# RP2350A.net
KiCad netlist of a schematic drawn in Altium Designer
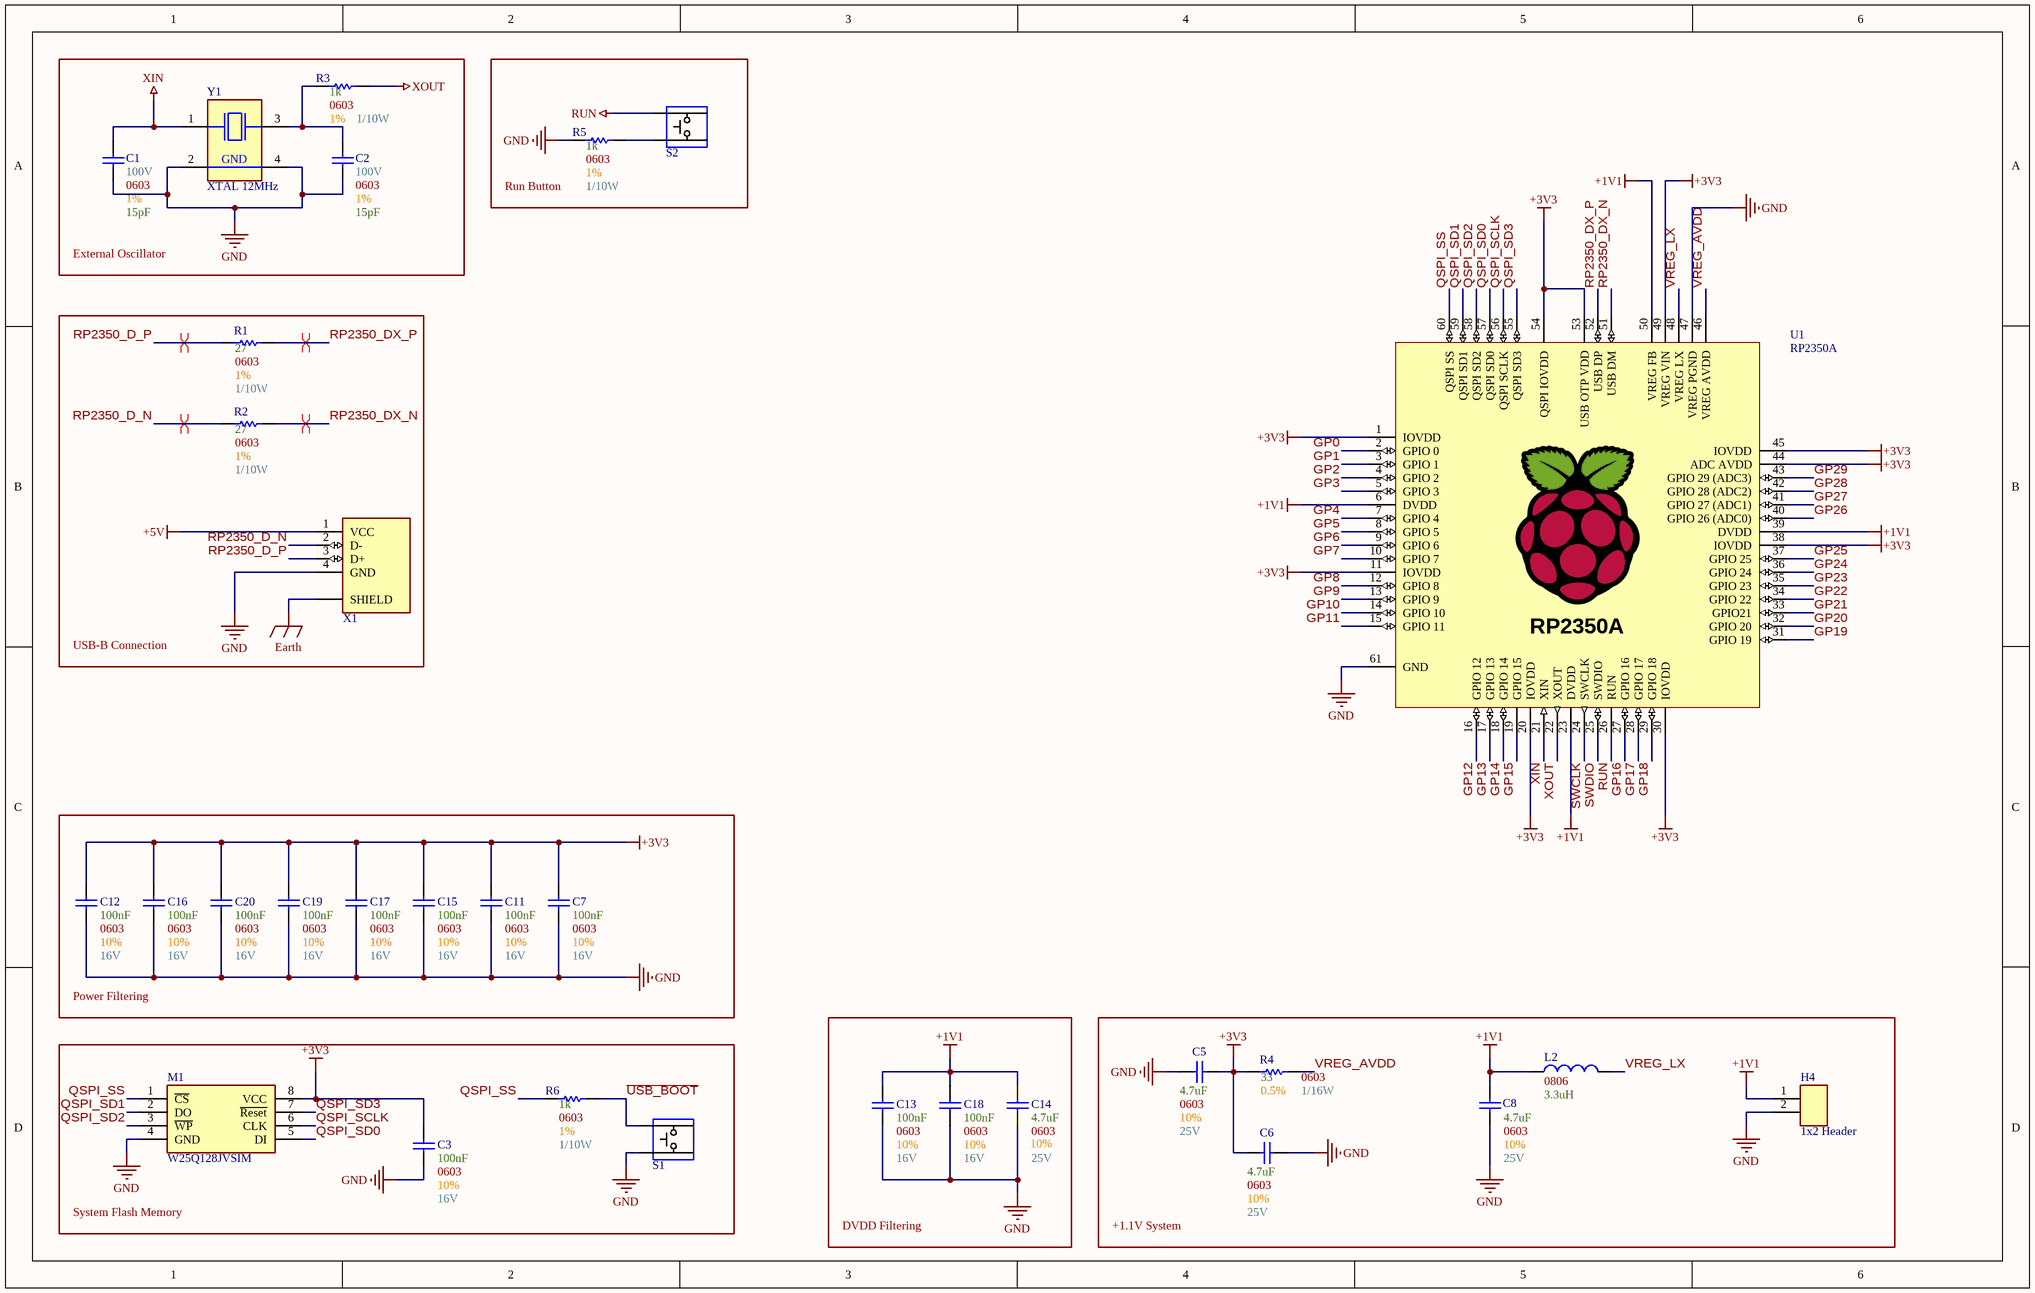
[diagram p0: RP2350A.SchDoc]

(export (version "E")
  (design (tool "Eeschema 10.0.6"))
  (components
    (comp (ref "C1")
      (value "[Cap] 0603 15pF 1% 100V")
      (footprint "[Cap] SMD 0603")
      (description "GCM1885C2A150FA16D")
      (fields
        (field (name "MAX VOLTAGE") "100V")
        (field (name "SIZE PACKAGE") "0603")
        (field (name "TOLERANCE") "1%")
        (field (name "CAPACITANCE") "15pF")
      )
      (libsource (lib "Capacitors") (part "[Cap] 0603 15pF 1% 100V"))
    )
    (comp (ref "C2")
      (value "[Cap] 0603 15pF 1% 100V")
      (footprint "[Cap] SMD 0603")
      (description "GCM1885C2A150FA16D")
      (fields
        (field (name "MAX VOLTAGE") "100V")
        (field (name "SIZE PACKAGE") "0603")
        (field (name "TOLERANCE") "1%")
        (field (name "CAPACITANCE") "15pF")
      )
      (libsource (lib "Capacitors") (part "[Cap] 0603 15pF 1% 100V"))
    )
    (comp (ref "C3")
      (value "[Cap] 0603 0.1uF 10% 16V")
      (footprint "[Cap] SMD 0603")
      (description "CC0603KRX7R7BB104")
      (fields
        (field (name "MAX VOLTAGE") "16V")
        (field (name "SIZE PACKAGE") "0603")
        (field (name "TOLERANCE") "10%")
        (field (name "CAPACITANCE") "100nF")
      )
      (libsource (lib "Capacitors") (part "[Cap] 0603 0.1uF 10% 16V"))
    )
    (comp (ref "C5")
      (value "[Cap] 0603 4.7uF 10% 25V")
      (footprint "[Cap] SMD 0603")
      (description "GRM188R61E475KE11D")
      (fields
        (field (name "MAX VOLTAGE") "25V")
        (field (name "SIZE PACKAGE") "0603")
        (field (name "TOLERANCE") "10%")
        (field (name "CAPACITANCE") "4.7uF")
      )
      (libsource (lib "Capacitors") (part "[Cap] 0603 4.7uF 10% 25V"))
    )
    (comp (ref "C6")
      (value "[Cap] 0603 4.7uF 10% 25V")
      (footprint "[Cap] SMD 0603")
      (description "GRM188R61E475KE11D")
      (fields
        (field (name "MAX VOLTAGE") "25V")
        (field (name "SIZE PACKAGE") "0603")
        (field (name "TOLERANCE") "10%")
        (field (name "CAPACITANCE") "4.7uF")
      )
      (libsource (lib "Capacitors") (part "[Cap] 0603 4.7uF 10% 25V"))
    )
    (comp (ref "C7")
      (value "[Cap] 0603 0.1uF 10% 16V")
      (footprint "[Cap] SMD 0603")
      (description "CC0603KRX7R7BB104")
      (fields
        (field (name "MAX VOLTAGE") "16V")
        (field (name "SIZE PACKAGE") "0603")
        (field (name "TOLERANCE") "10%")
        (field (name "CAPACITANCE") "100nF")
      )
      (libsource (lib "Capacitors") (part "[Cap] 0603 0.1uF 10% 16V"))
    )
    (comp (ref "C8")
      (value "[Cap] 0603 4.7uF 10% 25V")
      (footprint "[Cap] SMD 0603")
      (description "GRM188R61E475KE11D")
      (fields
        (field (name "MAX VOLTAGE") "25V")
        (field (name "SIZE PACKAGE") "0603")
        (field (name "TOLERANCE") "10%")
        (field (name "CAPACITANCE") "4.7uF")
      )
      (libsource (lib "Capacitors") (part "[Cap] 0603 4.7uF 10% 25V"))
    )
    (comp (ref "C11")
      (value "[Cap] 0603 0.1uF 10% 16V")
      (footprint "[Cap] SMD 0603")
      (description "CC0603KRX7R7BB104")
      (fields
        (field (name "MAX VOLTAGE") "16V")
        (field (name "SIZE PACKAGE") "0603")
        (field (name "TOLERANCE") "10%")
        (field (name "CAPACITANCE") "100nF")
      )
      (libsource (lib "Capacitors") (part "[Cap] 0603 0.1uF 10% 16V"))
    )
    (comp (ref "C12")
      (value "[Cap] 0603 0.1uF 10% 16V")
      (footprint "[Cap] SMD 0603")
      (description "CC0603KRX7R7BB104")
      (fields
        (field (name "MAX VOLTAGE") "16V")
        (field (name "SIZE PACKAGE") "0603")
        (field (name "TOLERANCE") "10%")
        (field (name "CAPACITANCE") "100nF")
      )
      (libsource (lib "Capacitors") (part "[Cap] 0603 0.1uF 10% 16V"))
    )
    (comp (ref "C13")
      (value "[Cap] 0603 0.1uF 10% 16V")
      (footprint "[Cap] SMD 0603")
      (description "CC0603KRX7R7BB104")
      (fields
        (field (name "MAX VOLTAGE") "16V")
        (field (name "SIZE PACKAGE") "0603")
        (field (name "TOLERANCE") "10%")
        (field (name "CAPACITANCE") "100nF")
      )
      (libsource (lib "Capacitors") (part "[Cap] 0603 0.1uF 10% 16V"))
    )
    (comp (ref "C14")
      (value "[Cap] 0603 4.7uF 10% 25V")
      (footprint "[Cap] SMD 0603")
      (description "GRM188R61E475KE11D")
      (fields
        (field (name "MAX VOLTAGE") "25V")
        (field (name "SIZE PACKAGE") "0603")
        (field (name "TOLERANCE") "10%")
        (field (name "CAPACITANCE") "4.7uF")
      )
      (libsource (lib "Capacitors") (part "[Cap] 0603 4.7uF 10% 25V"))
    )
    (comp (ref "C15")
      (value "[Cap] 0603 0.1uF 10% 16V")
      (footprint "[Cap] SMD 0603")
      (description "CC0603KRX7R7BB104")
      (fields
        (field (name "MAX VOLTAGE") "16V")
        (field (name "SIZE PACKAGE") "0603")
        (field (name "TOLERANCE") "10%")
        (field (name "CAPACITANCE") "100nF")
      )
      (libsource (lib "Capacitors") (part "[Cap] 0603 0.1uF 10% 16V"))
    )
    (comp (ref "C16")
      (value "[Cap] 0603 0.1uF 10% 16V")
      (footprint "[Cap] SMD 0603")
      (description "CC0603KRX7R7BB104")
      (fields
        (field (name "MAX VOLTAGE") "16V")
        (field (name "SIZE PACKAGE") "0603")
        (field (name "TOLERANCE") "10%")
        (field (name "CAPACITANCE") "100nF")
      )
      (libsource (lib "Capacitors") (part "[Cap] 0603 0.1uF 10% 16V"))
    )
    (comp (ref "C17")
      (value "[Cap] 0603 0.1uF 10% 16V")
      (footprint "[Cap] SMD 0603")
      (description "CC0603KRX7R7BB104")
      (fields
        (field (name "MAX VOLTAGE") "16V")
        (field (name "SIZE PACKAGE") "0603")
        (field (name "TOLERANCE") "10%")
        (field (name "CAPACITANCE") "100nF")
      )
      (libsource (lib "Capacitors") (part "[Cap] 0603 0.1uF 10% 16V"))
    )
    (comp (ref "C18")
      (value "[Cap] 0603 0.1uF 10% 16V")
      (footprint "[Cap] SMD 0603")
      (description "CC0603KRX7R7BB104")
      (fields
        (field (name "MAX VOLTAGE") "16V")
        (field (name "SIZE PACKAGE") "0603")
        (field (name "TOLERANCE") "10%")
        (field (name "CAPACITANCE") "100nF")
      )
      (libsource (lib "Capacitors") (part "[Cap] 0603 0.1uF 10% 16V"))
    )
    (comp (ref "C19")
      (value "[Cap] 0603 0.1uF 10% 16V")
      (footprint "[Cap] SMD 0603")
      (description "CC0603KRX7R7BB104")
      (fields
        (field (name "MAX VOLTAGE") "16V")
        (field (name "SIZE PACKAGE") "0603")
        (field (name "TOLERANCE") "10%")
        (field (name "CAPACITANCE") "100nF")
      )
      (libsource (lib "Capacitors") (part "[Cap] 0603 0.1uF 10% 16V"))
    )
    (comp (ref "C20")
      (value "[Cap] 0603 0.1uF 10% 16V")
      (footprint "[Cap] SMD 0603")
      (description "CC0603KRX7R7BB104")
      (fields
        (field (name "MAX VOLTAGE") "16V")
        (field (name "SIZE PACKAGE") "0603")
        (field (name "TOLERANCE") "10%")
        (field (name "CAPACITANCE") "100nF")
      )
      (libsource (lib "Capacitors") (part "[Cap] 0603 0.1uF 10% 16V"))
    )
    (comp (ref "H4")
      (value "1x2 Header")
      (footprint "[Header] 1x2 Male")
      (description "2.54mm pitch")
      (libsource (lib "Connectors") (part "[Header] 1x2 Male"))
    )
    (comp (ref "L2")
      (value "[3.3uH] SMD 0806 2.1A")
      (footprint "[Inductor] SMD 0806")
      (description "AOTA-B201610S3R3-101-T")
      (fields (field (name "PACKAGE") "0806") (field (name "INDUCTANCE") "3.3uH"))
      (libsource (lib "Inductors") (part "[3.3uH] SMD 0806 2.1A"))
    )
    (comp (ref "M1")
      (value "W25Q128JVSIM")
      (footprint "[Flash] 128MBit")
      (libsource (lib "Memory") (part "[Flash] 128MBit"))
    )
    (comp (ref "R1")
      (value "[27] SMD 0603 1% 1/10W")
      (footprint "[Res] SMD 0603")
      (description "MCT06030C2709FP500")
      (fields
        (field (name "WATTAGE") "1/10W")
        (field (name "TOLERANCE") "1%")
        (field (name "RESISTANCE") "27")
        (field (name "SIZE PACKAGE") "0603")
      )
      (libsource (lib "Resistors") (part "[27] SMD 0603 1% 1/10W"))
    )
    (comp (ref "R2")
      (value "[27] SMD 0603 1% 1/10W")
      (footprint "[Res] SMD 0603")
      (description "MCT06030C2709FP500")
      (fields
        (field (name "WATTAGE") "1/10W")
        (field (name "TOLERANCE") "1%")
        (field (name "RESISTANCE") "27")
        (field (name "SIZE PACKAGE") "0603")
      )
      (libsource (lib "Resistors") (part "[27] SMD 0603 1% 1/10W"))
    )
    (comp (ref "R3")
      (value "[1k] SMD 0603 1% 1/10W")
      (footprint "[Res] SMD 0603")
      (description "RMCF0603FT1K00")
      (fields
        (field (name "WATTAGE") "1/10W")
        (field (name "TOLERANCE") "1%")
        (field (name "RESISTANCE") "1k")
        (field (name "SIZE PACKAGE") "0603")
      )
      (libsource (lib "Resistors") (part "[1k] SMD 0603 1% 1/10W"))
    )
    (comp (ref "R4")
      (value "[33] SMD 0603 0.5% 1/16W")
      (footprint "[Res] SMD 0603")
      (description "RR0816Q-330-D")
      (fields
        (field (name "WATTAGE") "1/16W")
        (field (name "TOLERANCE") "0.5%")
        (field (name "RESISTANCE") "33")
        (field (name "SIZE PACKAGE") "0603")
      )
      (libsource (lib "Resistors") (part "[33] SMD 0603 0.5% 1/16W"))
    )
    (comp (ref "R5")
      (value "[1k] SMD 0603 1% 1/10W")
      (footprint "[Res] SMD 0603")
      (description "RMCF0603FT1K00")
      (fields
        (field (name "WATTAGE") "1/10W")
        (field (name "TOLERANCE") "1%")
        (field (name "RESISTANCE") "1k")
        (field (name "SIZE PACKAGE") "0603")
      )
      (libsource (lib "Resistors") (part "[1k] SMD 0603 1% 1/10W"))
    )
    (comp (ref "R6")
      (value "[1k] SMD 0603 1% 1/10W")
      (footprint "[Res] SMD 0603")
      (description "RMCF0603FT1K00")
      (fields
        (field (name "WATTAGE") "1/10W")
        (field (name "TOLERANCE") "1%")
        (field (name "RESISTANCE") "1k")
        (field (name "SIZE PACKAGE") "0603")
      )
      (libsource (lib "Resistors") (part "[1k] SMD 0603 1% 1/10W"))
    )
    (comp (ref "S1")
      (value "Standard pushbutton")
      (footprint "[SPST] Pushbutton")
      (libsource (lib "Switches") (part "[SPST] Pushbutton"))
    )
    (comp (ref "S2")
      (value "Standard pushbutton")
      (footprint "[SPST] Pushbutton")
      (libsource (lib "Switches") (part "[SPST] Pushbutton"))
    )
    (comp (ref "U1")
      (value "RP2350A")
      (footprint "[MCU] RP2350A")
      (description "QFN-60 Package")
      (libsource (lib "MCUs") (part "[MCU] RP2350A"))
    )
    (comp (ref "X1")
      (value "USB-B")
      (footprint "[USB] Type-B")
      (description "USB-B-S-F-B-TH")
      (libsource (lib "Connectors") (part "[USB] Type-B"))
    )
    (comp (ref "Y1")
      (value "XTAL 12MHz")
      (footprint "[Crystal] SMD 12MHz")
      (description "815-ABM8-272-T3")
      (libsource (lib "Crystals and Oscillators") (part "[Crystal] SMD 12MHz"))
    )
  )
  (nets
    (net (code "1") (name "+1V1") (class "Default")
      (node (ref "C13") (pin "2") (pinfunction "2_2") (pintype "passive"))
      (node (ref "C14") (pin "2") (pinfunction "2_2") (pintype "passive"))
      (node (ref "C18") (pin "2") (pinfunction "2_2") (pintype "passive"))
      (node (ref "C8") (pin "1") (pinfunction "1_1") (pintype "passive"))
      (node (ref "H4") (pin "1") (pintype "passive"))
      (node (ref "L2") (pin "1") (pinfunction "1_1") (pintype "passive"))
      (node (ref "U1") (pin "23") (pinfunction "DVDD_23") (pintype "power_in"))
      (node (ref "U1") (pin "39") (pinfunction "DVDD_39") (pintype "power_in"))
      (node (ref "U1") (pin "50") (pinfunction "VREG_FB_50") (pintype "power_in"))
      (node (ref "U1") (pin "6") (pinfunction "DVDD_6") (pintype "power_in"))
    )
    (net (code "2") (name "+3V3") (class "Default")
      (node (ref "C11") (pin "2") (pinfunction "2_2") (pintype "passive"))
      (node (ref "C12") (pin "2") (pinfunction "2_2") (pintype "passive"))
      (node (ref "C15") (pin "2") (pinfunction "2_2") (pintype "passive"))
      (node (ref "C16") (pin "2") (pinfunction "2_2") (pintype "passive"))
      (node (ref "C17") (pin "2") (pinfunction "2_2") (pintype "passive"))
      (node (ref "C19") (pin "2") (pinfunction "2_2") (pintype "passive"))
      (node (ref "C20") (pin "2") (pinfunction "2_2") (pintype "passive"))
      (node (ref "C3") (pin "2") (pinfunction "2_2") (pintype "passive"))
      (node (ref "C5") (pin "1") (pinfunction "1_1") (pintype "passive"))
      (node (ref "C6") (pin "2") (pinfunction "2_2") (pintype "passive"))
      (node (ref "C7") (pin "2") (pinfunction "2_2") (pintype "passive"))
      (node (ref "M1") (pin "8") (pinfunction "VCC_8") (pintype "passive"))
      (node (ref "R4") (pin "1") (pinfunction "1_1") (pintype "passive"))
      (node (ref "U1") (pin "1") (pinfunction "IOVDD_1") (pintype "power_in"))
      (node (ref "U1") (pin "11") (pinfunction "IOVDD_11") (pintype "power_in"))
      (node (ref "U1") (pin "20") (pinfunction "IOVDD_20") (pintype "power_in"))
      (node (ref "U1") (pin "30") (pinfunction "IOVDD_30") (pintype "power_in"))
      (node (ref "U1") (pin "38") (pinfunction "IOVDD_38") (pintype "power_in"))
      (node (ref "U1") (pin "44") (pinfunction "ADC_AVDD_44") (pintype "power_in"))
      (node (ref "U1") (pin "45") (pinfunction "IOVDD_45") (pintype "power_in"))
      (node (ref "U1") (pin "49") (pinfunction "VREG_VIN_49") (pintype "power_in"))
      (node (ref "U1") (pin "53") (pinfunction "USB_OTP_VDD_53") (pintype "power_in"))
      (node (ref "U1") (pin "54") (pinfunction "QSPI_IOVDD_54") (pintype "power_in"))
    )
    (net (code "3") (name "+5V") (class "Default")
      (node (ref "X1") (pin "1") (pinfunction "VCC_1") (pintype "power_in"))
    )
    (net (code "4") (name "/GP0") (class "Default")
      (node (ref "U1") (pin "2") (pinfunction "GPIO_0_2") (pintype "bidirectional"))
    )
    (net (code "5") (name "/GP1") (class "Default")
      (node (ref "U1") (pin "3") (pinfunction "GPIO_1_3") (pintype "bidirectional"))
    )
    (net (code "6") (name "/GP2") (class "Default")
      (node (ref "U1") (pin "4") (pinfunction "GPIO_2_4") (pintype "bidirectional"))
    )
    (net (code "7") (name "/GP3") (class "Default")
      (node (ref "U1") (pin "5") (pinfunction "GPIO_3_5") (pintype "bidirectional"))
    )
    (net (code "8") (name "/GP4") (class "Default")
      (node (ref "U1") (pin "7") (pinfunction "GPIO_4_7") (pintype "bidirectional"))
    )
    (net (code "9") (name "/GP5") (class "Default")
      (node (ref "U1") (pin "8") (pinfunction "GPIO_5_8") (pintype "bidirectional"))
    )
    (net (code "10") (name "/GP6") (class "Default")
      (node (ref "U1") (pin "9") (pinfunction "GPIO_6_9") (pintype "bidirectional"))
    )
    (net (code "11") (name "/GP7") (class "Default")
      (node (ref "U1") (pin "10") (pinfunction "GPIO_7_10") (pintype "bidirectional"))
    )
    (net (code "12") (name "/GP8") (class "Default")
      (node (ref "U1") (pin "12") (pinfunction "GPIO_8_12") (pintype "bidirectional"))
    )
    (net (code "13") (name "/GP9") (class "Default")
      (node (ref "U1") (pin "13") (pinfunction "GPIO_9_13") (pintype "bidirectional"))
    )
    (net (code "14") (name "/GP10") (class "Default")
      (node (ref "U1") (pin "14") (pinfunction "GPIO_10_14") (pintype "bidirectional"))
    )
    (net (code "15") (name "/GP11") (class "Default")
      (node (ref "U1") (pin "15") (pinfunction "GPIO_11_15") (pintype "bidirectional"))
    )
    (net (code "16") (name "/GP12") (class "Default")
      (node (ref "U1") (pin "16") (pinfunction "GPIO_12_16") (pintype "bidirectional"))
    )
    (net (code "17") (name "/GP13") (class "Default")
      (node (ref "U1") (pin "17") (pinfunction "GPIO_13_17") (pintype "bidirectional"))
    )
    (net (code "18") (name "/GP14") (class "Default")
      (node (ref "U1") (pin "18") (pinfunction "GPIO_14_18") (pintype "bidirectional"))
    )
    (net (code "19") (name "/GP15") (class "Default")
      (node (ref "U1") (pin "19") (pinfunction "GPIO_15_19") (pintype "power_in"))
    )
    (net (code "20") (name "/GP16") (class "Default")
      (node (ref "U1") (pin "27") (pinfunction "GPIO_16_27") (pintype "bidirectional"))
    )
    (net (code "21") (name "/GP17") (class "Default")
      (node (ref "U1") (pin "28") (pinfunction "GPIO_17_28") (pintype "bidirectional"))
    )
    (net (code "22") (name "/GP18") (class "Default")
      (node (ref "U1") (pin "29") (pinfunction "GPIO_18_29") (pintype "bidirectional"))
    )
    (net (code "23") (name "/GP19") (class "Default")
      (node (ref "U1") (pin "31") (pinfunction "GPIO_19_31") (pintype "bidirectional"))
    )
    (net (code "24") (name "/GP20") (class "Default")
      (node (ref "U1") (pin "32") (pinfunction "GPIO_20_32") (pintype "bidirectional"))
    )
    (net (code "25") (name "/GP21") (class "Default")
      (node (ref "U1") (pin "33") (pinfunction "GPIO21_33") (pintype "bidirectional"))
    )
    (net (code "26") (name "/GP22") (class "Default")
      (node (ref "U1") (pin "34") (pinfunction "GPIO_22_34") (pintype "bidirectional"))
    )
    (net (code "27") (name "/GP23") (class "Default")
      (node (ref "U1") (pin "35") (pinfunction "GPIO_23_35") (pintype "bidirectional"))
    )
    (net (code "28") (name "/GP24") (class "Default")
      (node (ref "U1") (pin "36") (pinfunction "GPIO_24_36") (pintype "bidirectional"))
    )
    (net (code "29") (name "/GP25") (class "Default")
      (node (ref "U1") (pin "37") (pinfunction "GPIO_25_37") (pintype "bidirectional"))
    )
    (net (code "30") (name "/GP26") (class "Default")
      (node (ref "U1") (pin "40") (pinfunction "GPIO_26_(ADC0)_40") (pintype "bidirectional"))
    )
    (net (code "31") (name "/GP27") (class "Default")
      (node (ref "U1") (pin "41") (pinfunction "GPIO_27_(ADC1)_41") (pintype "bidirectional"))
    )
    (net (code "32") (name "/GP28") (class "Default")
      (node (ref "U1") (pin "42") (pinfunction "GPIO_28_(ADC2)_42") (pintype "bidirectional"))
    )
    (net (code "33") (name "/GP29") (class "Default")
      (node (ref "U1") (pin "43") (pinfunction "GPIO_29_(ADC3)_43") (pintype "bidirectional"))
    )
    (net (code "34") (name "/QSPI_SCLK") (class "Default")
      (node (ref "M1") (pin "6") (pinfunction "CLK_6") (pintype "passive"))
      (node (ref "U1") (pin "56") (pinfunction "QSPI_SCLK_56") (pintype "bidirectional"))
    )
    (net (code "35") (name "/QSPI_SD0") (class "Default")
      (node (ref "M1") (pin "5") (pinfunction "DI_5") (pintype "passive"))
      (node (ref "U1") (pin "57") (pinfunction "QSPI_SD0_57") (pintype "bidirectional"))
    )
    (net (code "36") (name "/QSPI_SD1") (class "Default")
      (node (ref "M1") (pin "2") (pinfunction "DO_2") (pintype "passive"))
      (node (ref "U1") (pin "59") (pinfunction "QSPI_SD1_59") (pintype "bidirectional"))
    )
    (net (code "37") (name "/QSPI_SD2") (class "Default")
      (node (ref "M1") (pin "3") (pinfunction "~{WP}_3") (pintype "passive"))
      (node (ref "U1") (pin "58") (pinfunction "QSPI_SD2_58") (pintype "bidirectional"))
    )
    (net (code "38") (name "/QSPI_SD3") (class "Default")
      (node (ref "M1") (pin "7") (pinfunction "~{Reset}_7") (pintype "passive"))
      (node (ref "U1") (pin "55") (pinfunction "QSPI_SD3_55") (pintype "bidirectional"))
    )
    (net (code "39") (name "/QSPI_SS") (class "Default")
      (node (ref "M1") (pin "1") (pinfunction "~{CS}_1") (pintype "passive"))
      (node (ref "R6") (pin "1") (pinfunction "1_1") (pintype "passive"))
      (node (ref "U1") (pin "60") (pinfunction "QSPI_SS_60") (pintype "bidirectional"))
    )
    (net (code "40") (name "/RP2350_DX_N") (class "Default")
      (node (ref "R2") (pin "2") (pinfunction "2_2") (pintype "passive"))
      (node (ref "U1") (pin "51") (pinfunction "USB_DM_51") (pintype "bidirectional"))
    )
    (net (code "41") (name "/RP2350_DX_P") (class "Default")
      (node (ref "R1") (pin "2") (pinfunction "2_2") (pintype "passive"))
      (node (ref "U1") (pin "52") (pinfunction "USB_DP_52") (pintype "bidirectional"))
    )
    (net (code "42") (name "/RP2350_D_N") (class "Default")
      (node (ref "R2") (pin "1") (pinfunction "1_1") (pintype "passive"))
      (node (ref "X1") (pin "2") (pinfunction "D-_2") (pintype "bidirectional"))
    )
    (net (code "43") (name "/RP2350_D_P") (class "Default")
      (node (ref "R1") (pin "1") (pinfunction "1_1") (pintype "passive"))
      (node (ref "X1") (pin "3") (pinfunction "D+_3") (pintype "bidirectional"))
    )
    (net (code "44") (name "/SWCLK") (class "Default")
      (node (ref "U1") (pin "24") (pinfunction "SWCLK_24") (pintype "output"))
    )
    (net (code "45") (name "/SWDIO") (class "Default")
      (node (ref "U1") (pin "25") (pinfunction "SWDIO_25") (pintype "bidirectional"))
    )
    (net (code "46") (name "/VREG_AVDD") (class "Default")
      (node (ref "R4") (pin "2") (pinfunction "2_2") (pintype "passive"))
      (node (ref "U1") (pin "46") (pinfunction "VREG_AVDD_46") (pintype "power_in"))
    )
    (net (code "47") (name "/VREG_LX") (class "Default")
      (node (ref "L2") (pin "2") (pinfunction "2_2") (pintype "passive"))
      (node (ref "U1") (pin "48") (pinfunction "VREG_LX_48") (pintype "power_in"))
    )
    (net (code "48") (name "/~{USB_BOOT}") (class "Default")
      (node (ref "R6") (pin "2") (pinfunction "2_2") (pintype "passive"))
      (node (ref "S1") (pin "1") (pintype "power_in"))
    )
    (net (code "49") (name "Earth") (class "Default")
      (node (ref "X1") (pin "MH") (pinfunction "SHIELD_MH") (pintype "passive"))
    )
    (net (code "50") (name "GND") (class "Default")
      (node (ref "C1") (pin "1") (pinfunction "1_1") (pintype "passive"))
      (node (ref "C11") (pin "1") (pinfunction "1_1") (pintype "passive"))
      (node (ref "C12") (pin "1") (pinfunction "1_1") (pintype "passive"))
      (node (ref "C13") (pin "1") (pinfunction "1_1") (pintype "passive"))
      (node (ref "C14") (pin "1") (pinfunction "1_1") (pintype "passive"))
      (node (ref "C15") (pin "1") (pinfunction "1_1") (pintype "passive"))
      (node (ref "C16") (pin "1") (pinfunction "1_1") (pintype "passive"))
      (node (ref "C17") (pin "1") (pinfunction "1_1") (pintype "passive"))
      (node (ref "C18") (pin "1") (pinfunction "1_1") (pintype "passive"))
      (node (ref "C19") (pin "1") (pinfunction "1_1") (pintype "passive"))
      (node (ref "C2") (pin "1") (pinfunction "1_1") (pintype "passive"))
      (node (ref "C20") (pin "1") (pinfunction "1_1") (pintype "passive"))
      (node (ref "C3") (pin "1") (pinfunction "1_1") (pintype "passive"))
      (node (ref "C5") (pin "2") (pinfunction "2_2") (pintype "passive"))
      (node (ref "C6") (pin "1") (pinfunction "1_1") (pintype "passive"))
      (node (ref "C7") (pin "1") (pinfunction "1_1") (pintype "passive"))
      (node (ref "C8") (pin "2") (pinfunction "2_2") (pintype "passive"))
      (node (ref "H4") (pin "2") (pintype "passive"))
      (node (ref "M1") (pin "4") (pinfunction "GND_4") (pintype "passive"))
      (node (ref "R5") (pin "1") (pinfunction "1_1") (pintype "passive"))
      (node (ref "S1") (pin "2") (pintype "power_in"))
      (node (ref "U1") (pin "47") (pinfunction "VREG_PGND_47") (pintype "power_in"))
      (node (ref "U1") (pin "61") (pinfunction "GND_61") (pintype "power_in"))
      (node (ref "X1") (pin "4") (pinfunction "GND_4") (pintype "power_in"))
      (node (ref "Y1") (pin "2") (pinfunction "GND_2") (pintype "power_in"))
      (node (ref "Y1") (pin "4") (pinfunction "GND_4") (pintype "power_in"))
    )
    (net (code "51") (name "Net-(R5-Pad2)") (class "Default")
      (node (ref "R5") (pin "2") (pinfunction "2_2") (pintype "passive"))
      (node (ref "S2") (pin "2") (pintype "power_in"))
    )
    (net (code "52") (name "Net-(Y1-XTAL2)") (class "Default")
      (node (ref "C2") (pin "2") (pinfunction "2_2") (pintype "passive"))
      (node (ref "R3") (pin "1") (pinfunction "1_1") (pintype "passive"))
      (node (ref "Y1") (pin "3") (pinfunction "XTAL2_3") (pintype "power_in"))
    )
    (net (code "53") (name "RUN") (class "Default")
      (node (ref "S2") (pin "1") (pintype "power_in"))
      (node (ref "U1") (pin "26") (pinfunction "RUN_26") (pintype "passive"))
    )
    (net (code "54") (name "XIN") (class "Default")
      (node (ref "C1") (pin "2") (pinfunction "2_2") (pintype "passive"))
      (node (ref "U1") (pin "21") (pinfunction "XIN_21") (pintype "input"))
      (node (ref "Y1") (pin "1") (pinfunction "XTAL1_1") (pintype "power_in"))
    )
    (net (code "55") (name "XOUT") (class "Default")
      (node (ref "R3") (pin "2") (pinfunction "2_2") (pintype "passive"))
      (node (ref "U1") (pin "22") (pinfunction "XOUT_22") (pintype "output"))
    )
  )
)
